# Zesilova.net
KiCad netlist of a schematic drawn in EAGLE
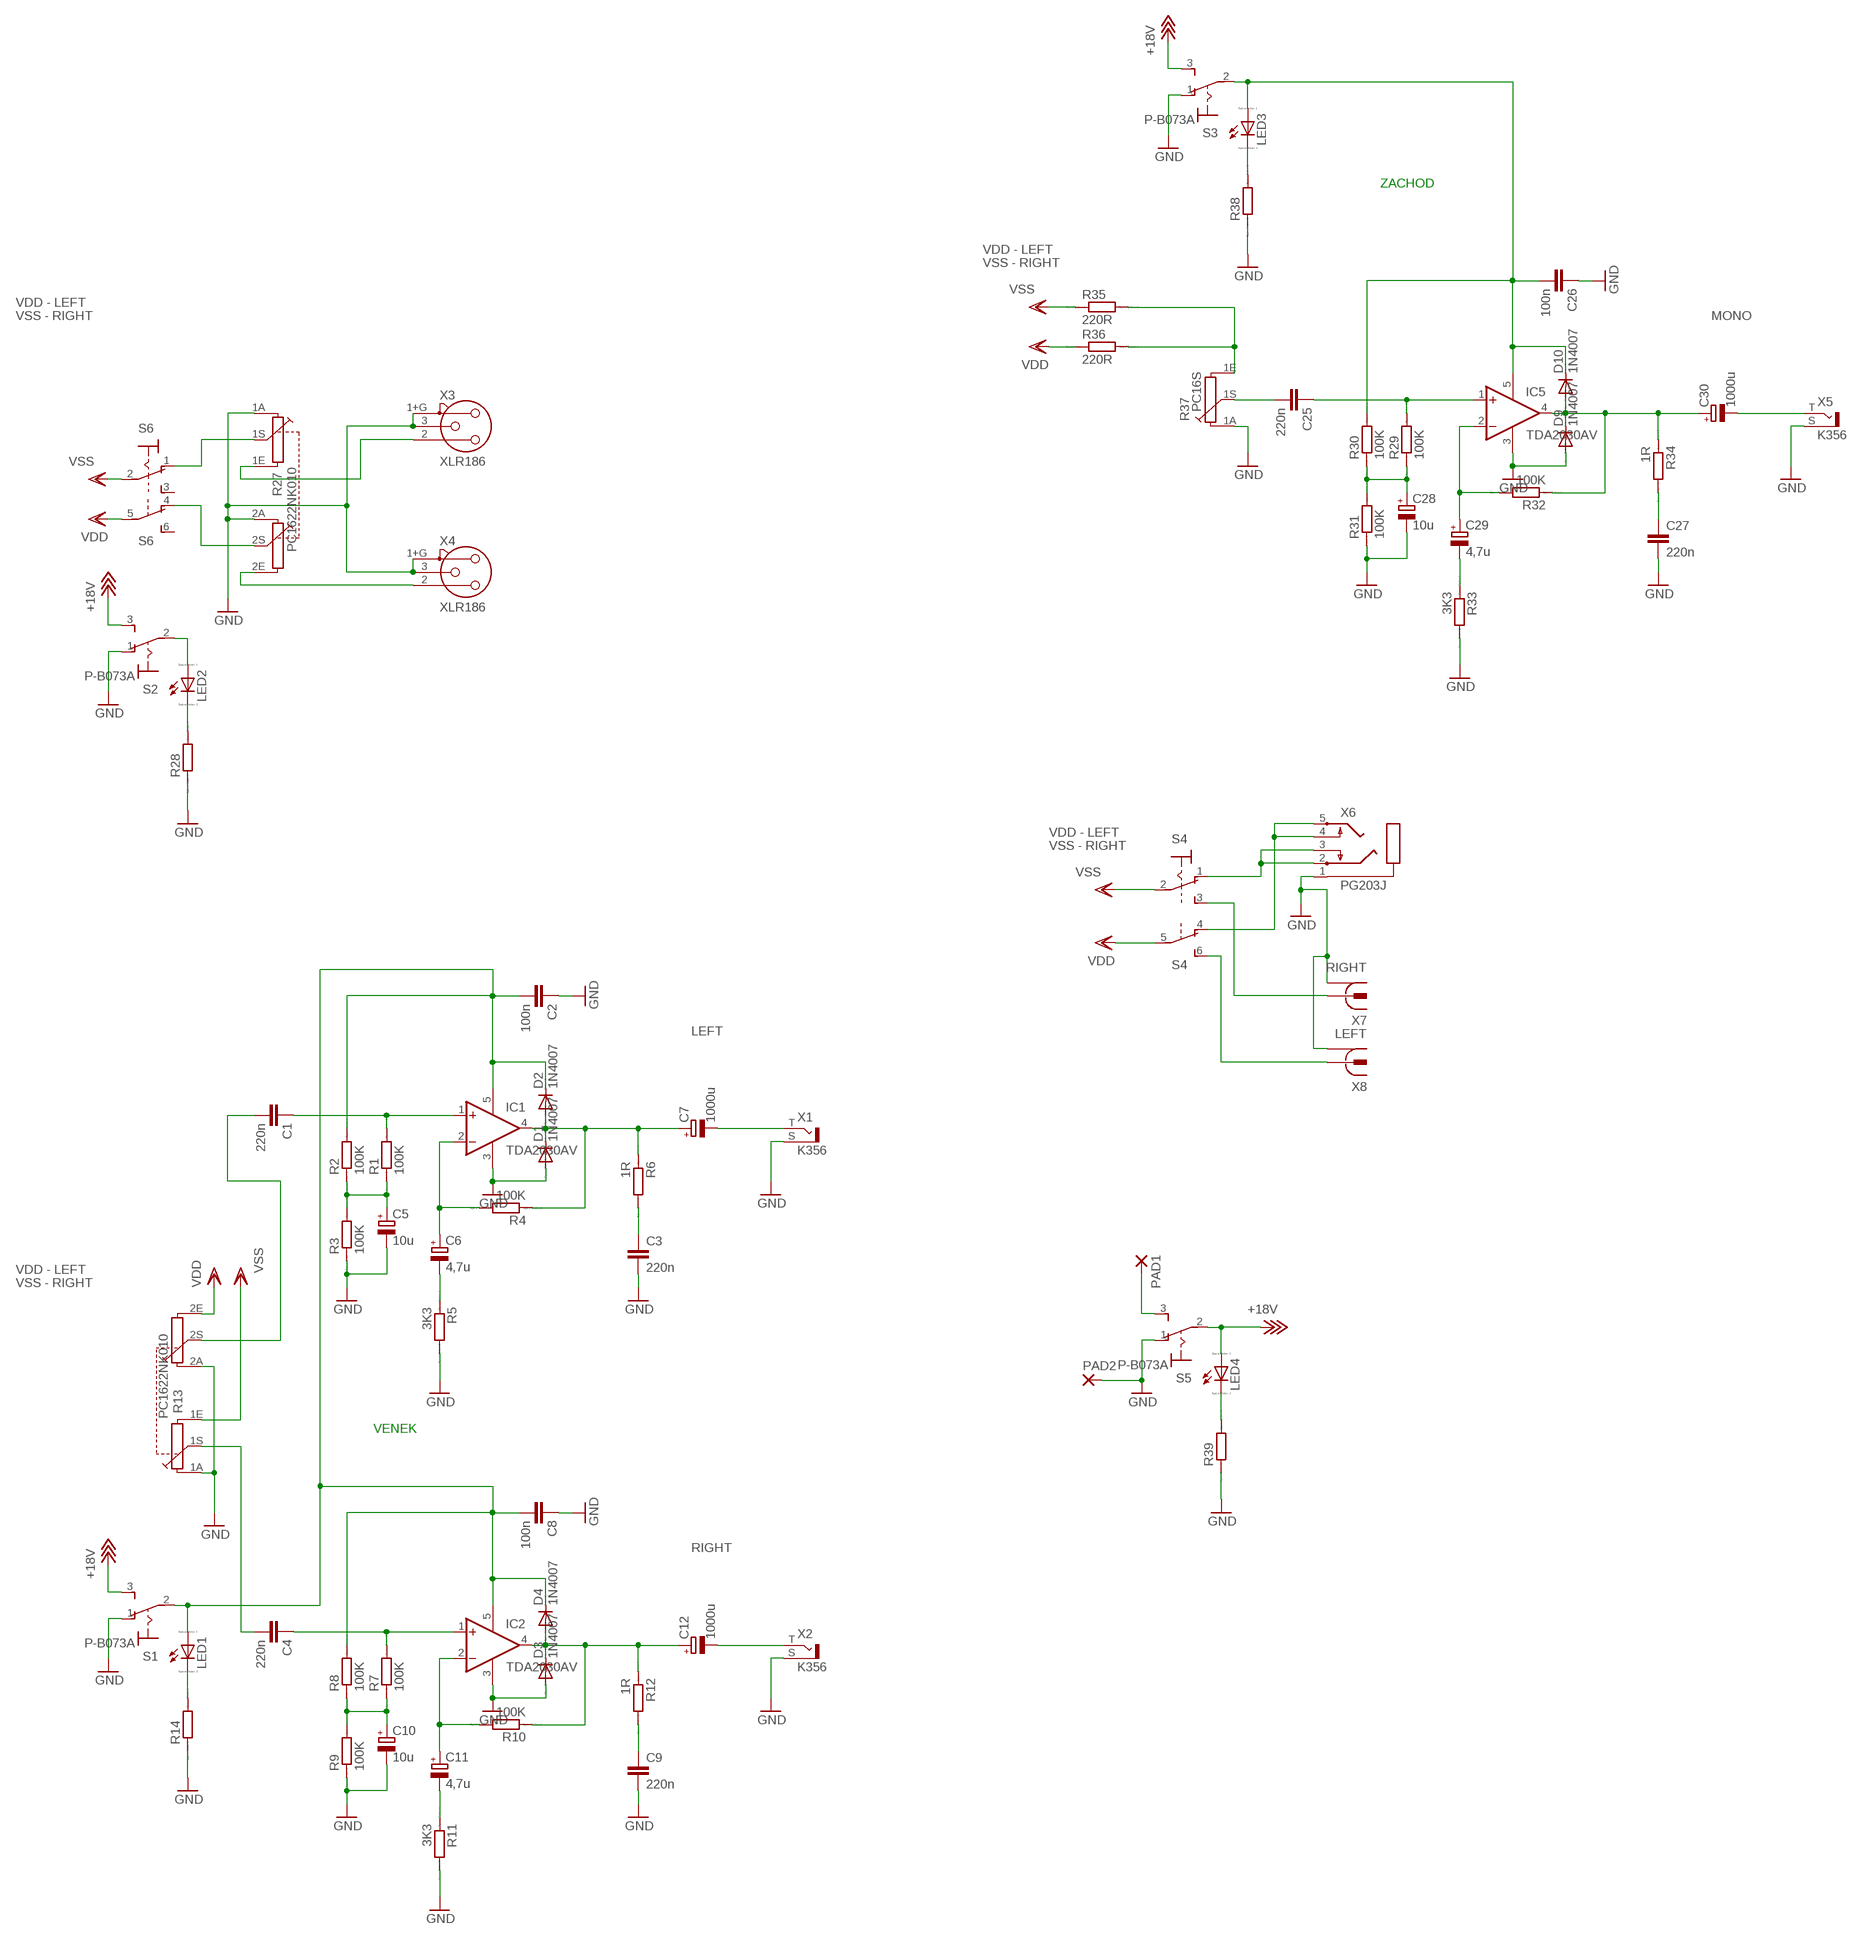
[diagram p0: schematic, sheet 1]

(export (version "E")
  (design (tool "Eeschema 10.0.6"))
  (components
    (comp (ref "C1")
      (value "220n")
      (footprint "eagle-import:C5B2.5")
      (libsource (lib "eagle-import") (part "C5/2.5"))
    )
    (comp (ref "C2")
      (value "100n")
      (footprint "eagle-import:C5B2.5")
      (libsource (lib "eagle-import") (part "C5/2.5"))
    )
    (comp (ref "C3")
      (value "220n")
      (footprint "eagle-import:C5B2.5")
      (libsource (lib "eagle-import") (part "C5/2.5"))
    )
    (comp (ref "C4")
      (value "220n")
      (footprint "eagle-import:C5B2.5")
      (libsource (lib "eagle-import") (part "C5/2.5"))
    )
    (comp (ref "C5")
      (value "10u")
      (footprint "eagle-import:E2-4")
      (libsource (lib "eagle-import") (part "CPOL-EUE2-4"))
    )
    (comp (ref "C6")
      (value "4,7u")
      (footprint "eagle-import:E2,5-6")
      (libsource (lib "eagle-import") (part "CPOL-EUE2.5-6"))
    )
    (comp (ref "C7")
      (value "1000u")
      (footprint "eagle-import:E3,5-8")
      (libsource (lib "eagle-import") (part "CPOL-EUE3.5-8"))
    )
    (comp (ref "C8")
      (value "100n")
      (footprint "eagle-import:C5B2.5")
      (libsource (lib "eagle-import") (part "C5/2.5"))
    )
    (comp (ref "C9")
      (value "220n")
      (footprint "eagle-import:C5B2.5")
      (libsource (lib "eagle-import") (part "C5/2.5"))
    )
    (comp (ref "C10")
      (value "10u")
      (footprint "eagle-import:E2-4")
      (libsource (lib "eagle-import") (part "CPOL-EUE2-4"))
    )
    (comp (ref "C11")
      (value "4,7u")
      (footprint "eagle-import:E2,5-6")
      (libsource (lib "eagle-import") (part "CPOL-EUE2.5-6"))
    )
    (comp (ref "C12")
      (value "1000u")
      (footprint "eagle-import:E3,5-8")
      (libsource (lib "eagle-import") (part "CPOL-EUE3.5-8"))
    )
    (comp (ref "C25")
      (value "220n")
      (footprint "eagle-import:C5B2.5")
      (libsource (lib "eagle-import") (part "C5/2.5"))
    )
    (comp (ref "C26")
      (value "100n")
      (footprint "eagle-import:C5B2.5")
      (libsource (lib "eagle-import") (part "C5/2.5"))
    )
    (comp (ref "C27")
      (value "220n")
      (footprint "eagle-import:C5B2.5")
      (libsource (lib "eagle-import") (part "C5/2.5"))
    )
    (comp (ref "C28")
      (value "10u")
      (footprint "eagle-import:E2-4")
      (libsource (lib "eagle-import") (part "CPOL-EUE2-4"))
    )
    (comp (ref "C29")
      (value "4,7u")
      (footprint "eagle-import:E2,5-6")
      (libsource (lib "eagle-import") (part "CPOL-EUE2.5-6"))
    )
    (comp (ref "C30")
      (value "1000u")
      (footprint "eagle-import:E3,5-8")
      (libsource (lib "eagle-import") (part "CPOL-EUE3.5-8"))
    )
    (comp (ref "D1")
      (value "1N4007")
      (footprint "eagle-import:DO41-10")
      (libsource (lib "eagle-import") (part "1N4004"))
    )
    (comp (ref "D2")
      (value "1N4007")
      (footprint "eagle-import:DO41-10")
      (libsource (lib "eagle-import") (part "1N4004"))
    )
    (comp (ref "D3")
      (value "1N4007")
      (footprint "eagle-import:DO41-10")
      (libsource (lib "eagle-import") (part "1N4004"))
    )
    (comp (ref "D4")
      (value "1N4007")
      (footprint "eagle-import:DO41-10")
      (libsource (lib "eagle-import") (part "1N4004"))
    )
    (comp (ref "D9")
      (value "1N4007")
      (footprint "eagle-import:DO41-10")
      (libsource (lib "eagle-import") (part "1N4004"))
    )
    (comp (ref "D10")
      (value "1N4007")
      (footprint "eagle-import:DO41-10")
      (libsource (lib "eagle-import") (part "1N4004"))
    )
    (comp (ref "IC1")
      (value "TDA2030AV")
      (footprint "eagle-import:CB360")
      (libsource (lib "eagle-import") (part "TDA2003V"))
    )
    (comp (ref "IC2")
      (value "TDA2030AV")
      (footprint "eagle-import:CB360")
      (libsource (lib "eagle-import") (part "TDA2003V"))
    )
    (comp (ref "IC5")
      (value "TDA2030AV")
      (footprint "eagle-import:CB360")
      (libsource (lib "eagle-import") (part "TDA2003V"))
    )
    (comp (ref "LED1")
      (value "LED_ELD260")
      (footprint "eagle-import:LED_LD260")
      (libsource (lib "eagle-import") (part "LED_ELD260"))
    )
    (comp (ref "LED2")
      (value "LED_ELD260")
      (footprint "eagle-import:LED_LD260")
      (libsource (lib "eagle-import") (part "LED_ELD260"))
    )
    (comp (ref "LED3")
      (value "LED_ELD260")
      (footprint "eagle-import:LED_LD260")
      (libsource (lib "eagle-import") (part "LED_ELD260"))
    )
    (comp (ref "LED4")
      (value "LED_ELD260")
      (footprint "eagle-import:LED_LD260")
      (libsource (lib "eagle-import") (part "LED_ELD260"))
    )
    (comp (ref "PAD1")
      (value "3,81/1,4")
      (footprint "eagle-import:3,81_1,4")
      (libsource (lib "eagle-import") (part "3,81/1,4"))
    )
    (comp (ref "PAD2")
      (value "3,81/1,4")
      (footprint "eagle-import:3,81_1,4")
      (libsource (lib "eagle-import") (part "3,81/1,4"))
    )
    (comp (ref "R1")
      (value "100K")
      (footprint "eagle-import:0204_7")
      (libsource (lib "eagle-import") (part "R0204/7"))
    )
    (comp (ref "R2")
      (value "100K")
      (footprint "eagle-import:0204_7")
      (libsource (lib "eagle-import") (part "R0204/7"))
    )
    (comp (ref "R3")
      (value "100K")
      (footprint "eagle-import:0204_7")
      (libsource (lib "eagle-import") (part "R0204/7"))
    )
    (comp (ref "R4")
      (value "100K")
      (footprint "eagle-import:0204_7")
      (libsource (lib "eagle-import") (part "R0204/7"))
    )
    (comp (ref "R5")
      (value "3K3")
      (footprint "eagle-import:0204_7")
      (libsource (lib "eagle-import") (part "R0204/7"))
    )
    (comp (ref "R6")
      (value "1R")
      (footprint "eagle-import:0207_10")
      (libsource (lib "eagle-import") (part "R0207/10"))
    )
    (comp (ref "R7")
      (value "100K")
      (footprint "eagle-import:0204_7")
      (libsource (lib "eagle-import") (part "R0204/7"))
    )
    (comp (ref "R8")
      (value "100K")
      (footprint "eagle-import:0204_7")
      (libsource (lib "eagle-import") (part "R0204/7"))
    )
    (comp (ref "R9")
      (value "100K")
      (footprint "eagle-import:0204_7")
      (libsource (lib "eagle-import") (part "R0204/7"))
    )
    (comp (ref "R10")
      (value "100K")
      (footprint "eagle-import:0204_7")
      (libsource (lib "eagle-import") (part "R0204/7"))
    )
    (comp (ref "R11")
      (value "3K3")
      (footprint "eagle-import:0204_7")
      (libsource (lib "eagle-import") (part "R0204/7"))
    )
    (comp (ref "R12")
      (value "1R")
      (footprint "eagle-import:0207_10")
      (libsource (lib "eagle-import") (part "R0207/10"))
    )
    (comp (ref "R13")
      (value "PC1622NK010")
      (footprint "eagle-import:PC16D")
      (libsource (lib "eagle-import") (part "PC16D"))
    )
    (comp (ref "R14")
      (value "R0204/7")
      (footprint "eagle-import:0204_7")
      (libsource (lib "eagle-import") (part "R0204/7"))
    )
    (comp (ref "R27")
      (value "PC1622NK010")
      (footprint "eagle-import:PC16D")
      (libsource (lib "eagle-import") (part "PC16D"))
    )
    (comp (ref "R28")
      (value "R0204/7")
      (footprint "eagle-import:0204_7")
      (libsource (lib "eagle-import") (part "R0204/7"))
    )
    (comp (ref "R29")
      (value "100K")
      (footprint "eagle-import:0204_7")
      (libsource (lib "eagle-import") (part "R0204/7"))
    )
    (comp (ref "R30")
      (value "100K")
      (footprint "eagle-import:0204_7")
      (libsource (lib "eagle-import") (part "R0204/7"))
    )
    (comp (ref "R31")
      (value "100K")
      (footprint "eagle-import:0204_7")
      (libsource (lib "eagle-import") (part "R0204/7"))
    )
    (comp (ref "R32")
      (value "100K")
      (footprint "eagle-import:0204_7")
      (libsource (lib "eagle-import") (part "R0204/7"))
    )
    (comp (ref "R33")
      (value "3K3")
      (footprint "eagle-import:0204_7")
      (libsource (lib "eagle-import") (part "R0204/7"))
    )
    (comp (ref "R34")
      (value "1R")
      (footprint "eagle-import:0207_10")
      (libsource (lib "eagle-import") (part "R0207/10"))
    )
    (comp (ref "R35")
      (value "220R")
      (footprint "eagle-import:0204_7")
      (libsource (lib "eagle-import") (part "R0204/7"))
    )
    (comp (ref "R36")
      (value "220R")
      (footprint "eagle-import:0204_7")
      (libsource (lib "eagle-import") (part "R0204/7"))
    )
    (comp (ref "R37")
      (value "PC16S")
      (footprint "eagle-import:PC16S")
      (libsource (lib "eagle-import") (part "PC16S"))
    )
    (comp (ref "R38")
      (value "R0204/7")
      (footprint "eagle-import:0204_7")
      (libsource (lib "eagle-import") (part "R0204/7"))
    )
    (comp (ref "R39")
      (value "R0204/7")
      (footprint "eagle-import:0204_7")
      (libsource (lib "eagle-import") (part "R0204/7"))
    )
    (comp (ref "S1")
      (value "P-B073A")
      (footprint "eagle-import:320-916")
      (libsource (lib "eagle-import") (part "320-916"))
    )
    (comp (ref "S2")
      (value "P-B073A")
      (footprint "eagle-import:320-916")
      (libsource (lib "eagle-import") (part "320-916"))
    )
    (comp (ref "S3")
      (value "P-B073A")
      (footprint "eagle-import:320-916")
      (libsource (lib "eagle-import") (part "320-916"))
    )
    (comp (ref "S4")
      (value "320-938")
      (footprint "eagle-import:320-938")
      (libsource (lib "eagle-import") (part "320-938"))
    )
    (comp (ref "S5")
      (value "P-B073A")
      (footprint "eagle-import:320-916")
      (libsource (lib "eagle-import") (part "320-916"))
    )
    (comp (ref "S6")
      (value "320-938")
      (footprint "eagle-import:320-938")
      (libsource (lib "eagle-import") (part "320-938"))
    )
    (comp (ref "X1")
      (value "K356")
      (footprint "eagle-import:RC-5231")
      (libsource (lib "eagle-import") (part "RC-5231"))
    )
    (comp (ref "X2")
      (value "K356")
      (footprint "eagle-import:RC-5231")
      (libsource (lib "eagle-import") (part "RC-5231"))
    )
    (comp (ref "X3")
      (value "XLR186")
      (footprint "eagle-import:NC3FAV1-0")
      (libsource (lib "eagle-import") (part "MC3?FAV1-0"))
    )
    (comp (ref "X4")
      (value "XLR186")
      (footprint "eagle-import:NC3FAV1-0")
      (libsource (lib "eagle-import") (part "MC3?FAV1-0"))
    )
    (comp (ref "X5")
      (value "K356")
      (footprint "eagle-import:RC-5231")
      (libsource (lib "eagle-import") (part "RC-5231"))
    )
    (comp (ref "X6")
      (value "PG203J")
      (footprint "eagle-import:PG203J")
      (libsource (lib "eagle-import") (part "PG203J"))
    )
    (comp (ref "X7")
      (value "RIGHT")
      (footprint "eagle-import:736880-49")
      (libsource (lib "eagle-import") (part "736880-49"))
    )
    (comp (ref "X8")
      (value "LEFT")
      (footprint "eagle-import:736880-49")
      (libsource (lib "eagle-import") (part "736880-49"))
    )
  )
  (nets
    (net (code "1") (name "+18V") (class "Default")
      (node (ref "LED4") (pin "A") (pinfunction "A_A") (pintype "passive"))
      (node (ref "S1") (pin "3") (pinfunction "S_3") (pintype "passive"))
      (node (ref "S2") (pin "3") (pinfunction "S_3") (pintype "passive"))
      (node (ref "S3") (pin "3") (pinfunction "S_3") (pintype "passive"))
      (node (ref "S5") (pin "2") (pinfunction "P_2") (pintype "passive"))
    )
    (net (code "2") (name "GND") (class "Default")
      (node (ref "C10") (pin "-") (pinfunction "-_-") (pintype "passive"))
      (node (ref "C2") (pin "1") (pinfunction "1_1") (pintype "passive"))
      (node (ref "C26") (pin "1") (pinfunction "1_1") (pintype "passive"))
      (node (ref "C27") (pin "2") (pinfunction "2_2") (pintype "passive"))
      (node (ref "C28") (pin "-") (pinfunction "-_-") (pintype "passive"))
      (node (ref "C3") (pin "2") (pinfunction "2_2") (pintype "passive"))
      (node (ref "C5") (pin "-") (pinfunction "-_-") (pintype "passive"))
      (node (ref "C8") (pin "1") (pinfunction "1_1") (pintype "passive"))
      (node (ref "C9") (pin "2") (pinfunction "2_2") (pintype "passive"))
      (node (ref "D1") (pin "A") (pinfunction "A_A") (pintype "passive"))
      (node (ref "D3") (pin "A") (pinfunction "A_A") (pintype "passive"))
      (node (ref "D9") (pin "A") (pinfunction "A_A") (pintype "passive"))
      (node (ref "IC1") (pin "3") (pinfunction "GND_3") (pintype "power_in"))
      (node (ref "IC2") (pin "3") (pinfunction "GND_3") (pintype "power_in"))
      (node (ref "IC5") (pin "3") (pinfunction "GND_3") (pintype "power_in"))
      (node (ref "PAD2") (pin "1") (pinfunction "P_1") (pintype "passive"))
      (node (ref "R11") (pin "2") (pinfunction "2_2") (pintype "passive"))
      (node (ref "R13") (pin "1A") (pinfunction "1A_1A") (pintype "passive"))
      (node (ref "R13") (pin "2A") (pinfunction "2A_2A") (pintype "passive"))
      (node (ref "R14") (pin "1") (pinfunction "1_1") (pintype "passive"))
      (node (ref "R27") (pin "1A") (pinfunction "1A_1A") (pintype "passive"))
      (node (ref "R27") (pin "2A") (pinfunction "2A_2A") (pintype "passive"))
      (node (ref "R28") (pin "1") (pinfunction "1_1") (pintype "passive"))
      (node (ref "R3") (pin "1") (pinfunction "1_1") (pintype "passive"))
      (node (ref "R31") (pin "1") (pinfunction "1_1") (pintype "passive"))
      (node (ref "R33") (pin "2") (pinfunction "2_2") (pintype "passive"))
      (node (ref "R37") (pin "1A") (pinfunction "1A_1A") (pintype "passive"))
      (node (ref "R38") (pin "1") (pinfunction "1_1") (pintype "passive"))
      (node (ref "R39") (pin "1") (pinfunction "1_1") (pintype "passive"))
      (node (ref "R5") (pin "2") (pinfunction "2_2") (pintype "passive"))
      (node (ref "R9") (pin "1") (pinfunction "1_1") (pintype "passive"))
      (node (ref "S1") (pin "1") (pinfunction "O_1") (pintype "passive"))
      (node (ref "S2") (pin "1") (pinfunction "O_1") (pintype "passive"))
      (node (ref "S3") (pin "1") (pinfunction "O_1") (pintype "passive"))
      (node (ref "S5") (pin "1") (pinfunction "O_1") (pintype "passive"))
      (node (ref "X1") (pin "S") (pinfunction "S_S") (pintype "passive"))
      (node (ref "X2") (pin "S") (pinfunction "S_S") (pintype "passive"))
      (node (ref "X3") (pin "1+G") (pinfunction "1_1+G") (pintype "passive"))
      (node (ref "X3") (pin "3") (pinfunction "3_3") (pintype "passive"))
      (node (ref "X4") (pin "1+G") (pinfunction "1_1+G") (pintype "passive"))
      (node (ref "X4") (pin "3") (pinfunction "3_3") (pintype "passive"))
      (node (ref "X5") (pin "S") (pinfunction "S_S") (pintype "passive"))
      (node (ref "X6") (pin "1") (pinfunction "1_1") (pintype "passive"))
      (node (ref "X7") (pin "1") (pinfunction "1_1") (pintype "passive"))
      (node (ref "X7") (pin "1@1") (pinfunction "1_1@1") (pintype "passive"))
      (node (ref "X7") (pin "1@2") (pinfunction "1_1@2") (pintype "passive"))
      (node (ref "X8") (pin "1") (pinfunction "1_1") (pintype "passive"))
      (node (ref "X8") (pin "1@1") (pinfunction "1_1@1") (pintype "passive"))
      (node (ref "X8") (pin "1@2") (pinfunction "1_1@2") (pintype "passive"))
    )
    (net (code "3") (name "Net-(C1-Pad2)") (class "Default")
      (node (ref "C1") (pin "2") (pinfunction "2_2") (pintype "passive"))
      (node (ref "R13") (pin "2S") (pinfunction "2S_2S") (pintype "passive"))
    )
    (net (code "4") (name "Net-(C3-Pad1)") (class "Default")
      (node (ref "C3") (pin "1") (pinfunction "1_1") (pintype "passive"))
      (node (ref "R6") (pin "2") (pinfunction "2_2") (pintype "passive"))
    )
    (net (code "5") (name "Net-(C4-Pad2)") (class "Default")
      (node (ref "C4") (pin "2") (pinfunction "2_2") (pintype "passive"))
      (node (ref "R13") (pin "1S") (pinfunction "1S_1S") (pintype "passive"))
    )
    (net (code "6") (name "Net-(C5-Pad+)") (class "Default")
      (node (ref "C5") (pin "+") (pinfunction "+_+") (pintype "passive"))
      (node (ref "R1") (pin "1") (pinfunction "1_1") (pintype "passive"))
      (node (ref "R2") (pin "1") (pinfunction "1_1") (pintype "passive"))
      (node (ref "R3") (pin "2") (pinfunction "2_2") (pintype "passive"))
    )
    (net (code "7") (name "Net-(C6-Pad-)") (class "Default")
      (node (ref "C6") (pin "-") (pinfunction "-_-") (pintype "passive"))
      (node (ref "R5") (pin "1") (pinfunction "1_1") (pintype "passive"))
    )
    (net (code "8") (name "Net-(C7-Pad-)") (class "Default")
      (node (ref "C7") (pin "-") (pinfunction "-_-") (pintype "passive"))
      (node (ref "X1") (pin "T") (pinfunction "T_T") (pintype "passive"))
    )
    (net (code "9") (name "Net-(C9-Pad1)") (class "Default")
      (node (ref "C9") (pin "1") (pinfunction "1_1") (pintype "passive"))
      (node (ref "R12") (pin "2") (pinfunction "2_2") (pintype "passive"))
    )
    (net (code "10") (name "Net-(C10-Pad+)") (class "Default")
      (node (ref "C10") (pin "+") (pinfunction "+_+") (pintype "passive"))
      (node (ref "R7") (pin "1") (pinfunction "1_1") (pintype "passive"))
      (node (ref "R8") (pin "1") (pinfunction "1_1") (pintype "passive"))
      (node (ref "R9") (pin "2") (pinfunction "2_2") (pintype "passive"))
    )
    (net (code "11") (name "Net-(C11-Pad-)") (class "Default")
      (node (ref "C11") (pin "-") (pinfunction "-_-") (pintype "passive"))
      (node (ref "R11") (pin "1") (pinfunction "1_1") (pintype "passive"))
    )
    (net (code "12") (name "Net-(C12-Pad-)") (class "Default")
      (node (ref "C12") (pin "-") (pinfunction "-_-") (pintype "passive"))
      (node (ref "X2") (pin "T") (pinfunction "T_T") (pintype "passive"))
    )
    (net (code "13") (name "Net-(C25-Pad2)") (class "Default")
      (node (ref "C25") (pin "2") (pinfunction "2_2") (pintype "passive"))
      (node (ref "R37") (pin "1S") (pinfunction "1S_1S") (pintype "passive"))
    )
    (net (code "14") (name "Net-(C27-Pad1)") (class "Default")
      (node (ref "C27") (pin "1") (pinfunction "1_1") (pintype "passive"))
      (node (ref "R34") (pin "2") (pinfunction "2_2") (pintype "passive"))
    )
    (net (code "15") (name "Net-(C28-Pad+)") (class "Default")
      (node (ref "C28") (pin "+") (pinfunction "+_+") (pintype "passive"))
      (node (ref "R29") (pin "1") (pinfunction "1_1") (pintype "passive"))
      (node (ref "R30") (pin "1") (pinfunction "1_1") (pintype "passive"))
      (node (ref "R31") (pin "2") (pinfunction "2_2") (pintype "passive"))
    )
    (net (code "16") (name "Net-(C29-Pad-)") (class "Default")
      (node (ref "C29") (pin "-") (pinfunction "-_-") (pintype "passive"))
      (node (ref "R33") (pin "1") (pinfunction "1_1") (pintype "passive"))
    )
    (net (code "17") (name "Net-(C30-Pad-)") (class "Default")
      (node (ref "C30") (pin "-") (pinfunction "-_-") (pintype "passive"))
      (node (ref "X5") (pin "T") (pinfunction "T_T") (pintype "passive"))
    )
    (net (code "18") (name "Net-(IC1-+IN)") (class "Default")
      (node (ref "C1") (pin "1") (pinfunction "1_1") (pintype "passive"))
      (node (ref "IC1") (pin "1") (pinfunction "+IN_1") (pintype "input"))
      (node (ref "R1") (pin "2") (pinfunction "2_2") (pintype "passive"))
    )
    (net (code "19") (name "Net-(IC1--IN)") (class "Default")
      (node (ref "C6") (pin "+") (pinfunction "+_+") (pintype "passive"))
      (node (ref "IC1") (pin "2") (pinfunction "-IN_2") (pintype "input"))
      (node (ref "R4") (pin "2") (pinfunction "2_2") (pintype "passive"))
    )
    (net (code "20") (name "Net-(IC1-OUT)") (class "Default")
      (node (ref "C7") (pin "+") (pinfunction "+_+") (pintype "passive"))
      (node (ref "D1") (pin "C") (pinfunction "C_C") (pintype "passive"))
      (node (ref "D2") (pin "A") (pinfunction "A_A") (pintype "passive"))
      (node (ref "IC1") (pin "4") (pinfunction "OUT_4") (pintype "output"))
      (node (ref "R4") (pin "1") (pinfunction "1_1") (pintype "passive"))
      (node (ref "R6") (pin "1") (pinfunction "1_1") (pintype "passive"))
    )
    (net (code "21") (name "Net-(IC1-V+)") (class "Default")
      (node (ref "C2") (pin "2") (pinfunction "2_2") (pintype "passive"))
      (node (ref "C8") (pin "2") (pinfunction "2_2") (pintype "passive"))
      (node (ref "D2") (pin "C") (pinfunction "C_C") (pintype "passive"))
      (node (ref "D4") (pin "C") (pinfunction "C_C") (pintype "passive"))
      (node (ref "IC1") (pin "5") (pinfunction "V+_5") (pintype "power_in"))
      (node (ref "IC2") (pin "5") (pinfunction "V+_5") (pintype "power_in"))
      (node (ref "LED1") (pin "A") (pinfunction "A_A") (pintype "passive"))
      (node (ref "R2") (pin "2") (pinfunction "2_2") (pintype "passive"))
      (node (ref "R8") (pin "2") (pinfunction "2_2") (pintype "passive"))
      (node (ref "S1") (pin "2") (pinfunction "P_2") (pintype "passive"))
    )
    (net (code "22") (name "Net-(IC2-+IN)") (class "Default")
      (node (ref "C4") (pin "1") (pinfunction "1_1") (pintype "passive"))
      (node (ref "IC2") (pin "1") (pinfunction "+IN_1") (pintype "input"))
      (node (ref "R7") (pin "2") (pinfunction "2_2") (pintype "passive"))
    )
    (net (code "23") (name "Net-(IC2--IN)") (class "Default")
      (node (ref "C11") (pin "+") (pinfunction "+_+") (pintype "passive"))
      (node (ref "IC2") (pin "2") (pinfunction "-IN_2") (pintype "input"))
      (node (ref "R10") (pin "2") (pinfunction "2_2") (pintype "passive"))
    )
    (net (code "24") (name "Net-(IC2-OUT)") (class "Default")
      (node (ref "C12") (pin "+") (pinfunction "+_+") (pintype "passive"))
      (node (ref "D3") (pin "C") (pinfunction "C_C") (pintype "passive"))
      (node (ref "D4") (pin "A") (pinfunction "A_A") (pintype "passive"))
      (node (ref "IC2") (pin "4") (pinfunction "OUT_4") (pintype "output"))
      (node (ref "R10") (pin "1") (pinfunction "1_1") (pintype "passive"))
      (node (ref "R12") (pin "1") (pinfunction "1_1") (pintype "passive"))
    )
    (net (code "25") (name "Net-(IC5-+IN)") (class "Default")
      (node (ref "C25") (pin "1") (pinfunction "1_1") (pintype "passive"))
      (node (ref "IC5") (pin "1") (pinfunction "+IN_1") (pintype "input"))
      (node (ref "R29") (pin "2") (pinfunction "2_2") (pintype "passive"))
    )
    (net (code "26") (name "Net-(IC5--IN)") (class "Default")
      (node (ref "C29") (pin "+") (pinfunction "+_+") (pintype "passive"))
      (node (ref "IC5") (pin "2") (pinfunction "-IN_2") (pintype "input"))
      (node (ref "R32") (pin "2") (pinfunction "2_2") (pintype "passive"))
    )
    (net (code "27") (name "Net-(IC5-OUT)") (class "Default")
      (node (ref "C30") (pin "+") (pinfunction "+_+") (pintype "passive"))
      (node (ref "D10") (pin "A") (pinfunction "A_A") (pintype "passive"))
      (node (ref "D9") (pin "C") (pinfunction "C_C") (pintype "passive"))
      (node (ref "IC5") (pin "4") (pinfunction "OUT_4") (pintype "output"))
      (node (ref "R32") (pin "1") (pinfunction "1_1") (pintype "passive"))
      (node (ref "R34") (pin "1") (pinfunction "1_1") (pintype "passive"))
    )
    (net (code "28") (name "Net-(IC5-V+)") (class "Default")
      (node (ref "C26") (pin "2") (pinfunction "2_2") (pintype "passive"))
      (node (ref "D10") (pin "C") (pinfunction "C_C") (pintype "passive"))
      (node (ref "IC5") (pin "5") (pinfunction "V+_5") (pintype "power_in"))
      (node (ref "LED3") (pin "A") (pinfunction "A_A") (pintype "passive"))
      (node (ref "R30") (pin "2") (pinfunction "2_2") (pintype "passive"))
      (node (ref "S3") (pin "2") (pinfunction "P_2") (pintype "passive"))
    )
    (net (code "29") (name "Net-(LED1-C)") (class "Default")
      (node (ref "LED1") (pin "K") (pinfunction "C_K") (pintype "passive"))
      (node (ref "R14") (pin "2") (pinfunction "2_2") (pintype "passive"))
    )
    (net (code "30") (name "Net-(LED2-C)") (class "Default")
      (node (ref "LED2") (pin "K") (pinfunction "C_K") (pintype "passive"))
      (node (ref "R28") (pin "2") (pinfunction "2_2") (pintype "passive"))
    )
    (net (code "31") (name "Net-(LED3-C)") (class "Default")
      (node (ref "LED3") (pin "K") (pinfunction "C_K") (pintype "passive"))
      (node (ref "R38") (pin "2") (pinfunction "2_2") (pintype "passive"))
    )
    (net (code "32") (name "Net-(LED4-C)") (class "Default")
      (node (ref "LED4") (pin "K") (pinfunction "C_K") (pintype "passive"))
      (node (ref "R39") (pin "2") (pinfunction "2_2") (pintype "passive"))
    )
    (net (code "33") (name "Net-(PAD1-P)") (class "Default")
      (node (ref "PAD1") (pin "1") (pinfunction "P_1") (pintype "passive"))
      (node (ref "S5") (pin "3") (pinfunction "S_3") (pintype "passive"))
    )
    (net (code "34") (name "Net-(R27-Pad1E)") (class "Default")
      (node (ref "R27") (pin "1E") (pinfunction "1E_1E") (pintype "passive"))
      (node (ref "X3") (pin "2") (pinfunction "2_2") (pintype "passive"))
    )
    (net (code "35") (name "Net-(R27-Pad2E)") (class "Default")
      (node (ref "R27") (pin "2E") (pinfunction "2E_2E") (pintype "passive"))
      (node (ref "X4") (pin "2") (pinfunction "2_2") (pintype "passive"))
    )
    (net (code "36") (name "Net-(R35-Pad2)") (class "Default")
      (node (ref "R35") (pin "2") (pinfunction "2_2") (pintype "passive"))
      (node (ref "R36") (pin "2") (pinfunction "2_2") (pintype "passive"))
      (node (ref "R37") (pin "1E") (pinfunction "1E_1E") (pintype "passive"))
    )
    (net (code "37") (name "Net-(S2-P)") (class "Default")
      (node (ref "LED2") (pin "A") (pinfunction "A_A") (pintype "passive"))
      (node (ref "S2") (pin "2") (pinfunction "P_2") (pintype "passive"))
    )
    (net (code "38") (name "Net-(S4A-O)") (class "Default")
      (node (ref "S4") (pin "1") (pinfunction "O_1") (pintype "passive"))
      (node (ref "X6") (pin "2") (pinfunction "2_2") (pintype "passive"))
      (node (ref "X6") (pin "3") (pinfunction "3_3") (pintype "passive"))
    )
    (net (code "39") (name "Net-(S4A-S)") (class "Default")
      (node (ref "S4") (pin "3") (pinfunction "S_3") (pintype "passive"))
      (node (ref "X7") (pin "2") (pinfunction "2_2") (pintype "passive"))
    )
    (net (code "40") (name "Net-(S4B-O)") (class "Default")
      (node (ref "S4") (pin "4") (pinfunction "O_4") (pintype "passive"))
      (node (ref "X6") (pin "4") (pinfunction "4_4") (pintype "passive"))
      (node (ref "X6") (pin "5") (pinfunction "5_5") (pintype "passive"))
    )
    (net (code "41") (name "Net-(S4B-S)") (class "Default")
      (node (ref "S4") (pin "6") (pinfunction "S_6") (pintype "passive"))
      (node (ref "X8") (pin "2") (pinfunction "2_2") (pintype "passive"))
    )
    (net (code "42") (name "Net-(S6A-O)") (class "Default")
      (node (ref "R27") (pin "1S") (pinfunction "1S_1S") (pintype "passive"))
      (node (ref "S6") (pin "1") (pinfunction "O_1") (pintype "passive"))
    )
    (net (code "43") (name "Net-(S6B-O)") (class "Default")
      (node (ref "R27") (pin "2S") (pinfunction "2S_2S") (pintype "passive"))
      (node (ref "S6") (pin "4") (pinfunction "O_4") (pintype "passive"))
    )
    (net (code "44") (name "VDD") (class "Default")
      (node (ref "R13") (pin "2E") (pinfunction "2E_2E") (pintype "passive"))
      (node (ref "R36") (pin "1") (pinfunction "1_1") (pintype "passive"))
      (node (ref "S4") (pin "5") (pinfunction "P_5") (pintype "passive"))
      (node (ref "S6") (pin "5") (pinfunction "P_5") (pintype "passive"))
    )
    (net (code "45") (name "VSS") (class "Default")
      (node (ref "R13") (pin "1E") (pinfunction "1E_1E") (pintype "passive"))
      (node (ref "R35") (pin "1") (pinfunction "1_1") (pintype "passive"))
      (node (ref "S4") (pin "2") (pinfunction "P_2") (pintype "passive"))
      (node (ref "S6") (pin "2") (pinfunction "P_2") (pintype "passive"))
    )
    (net (code "46") (name "unconnected-(S6A-S-Pad3)") (class "Default")
      (node (ref "S6") (pin "3") (pinfunction "S_3") (pintype "passive"))
    )
    (net (code "47") (name "unconnected-(S6B-S-Pad6)") (class "Default")
      (node (ref "S6") (pin "6") (pinfunction "S_6") (pintype "passive"))
    )
  )
)
